# Power_Distribution_-_Motor_Interface.net
KiCad netlist of a schematic drawn in Altium Designer
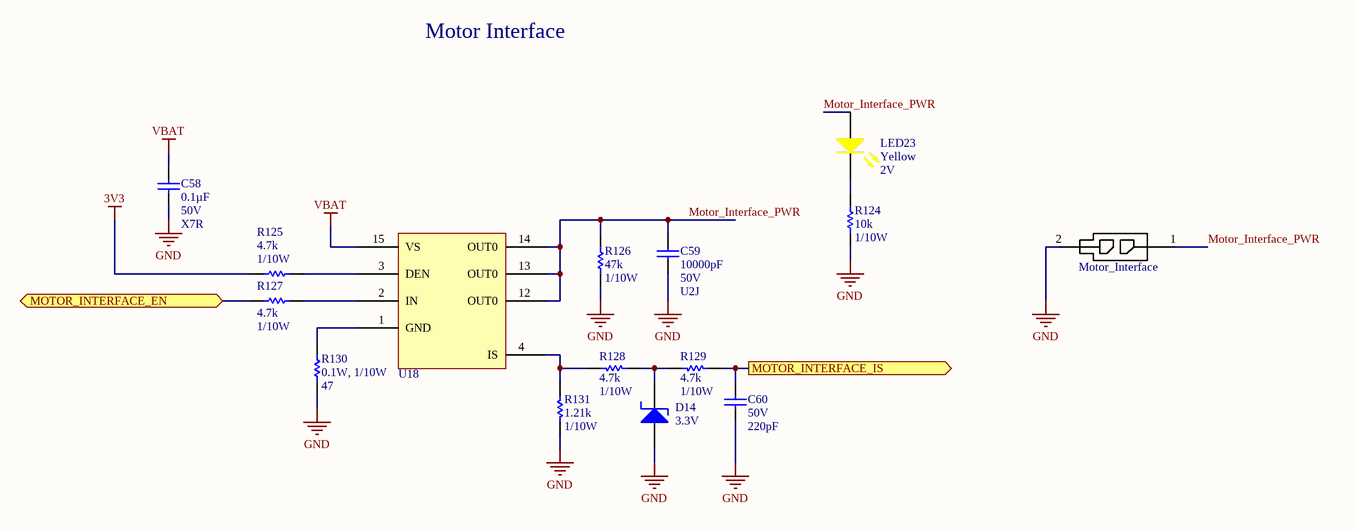
[diagram p0: Power Distribution - Motor Interface.SchDoc]

(export (version "E")
  (design (tool "Eeschema 10.0.6"))
  (components
    (comp (ref "C58")
      (value "CAP CER 0.1UF 50V 10% X7R 0603")
      (footprint "CAP, 0603")
      (description "0.10µF ±10% 50V Ceramic Capacitor X7R 0603 (1608 Metric)")
      (fields
        (field (name "TOLERANCE") "±10%")
        (field (name "CAPACITANCE") "0.1µF")
        (field (name "VOLTAGE") "50V")
        (field (name "TEMPERATURE COEFFICIENT") "X7R")
      )
      (libsource (lib "Schematic Diagrams") (part "CAP CER 0.1UF 50V 10% X7R 0603"))
    )
    (comp (ref "C59")
      (value "CAP CER 10nF 50V 5% X7R 0603")
      (footprint "CAP, 0603")
      (description "10000pF ±5% 50V Ceramic Capacitor U2J 0603 (1608 Metric)")
      (fields
        (field (name "TOLERANCE") "±5%")
        (field (name "CAPACITANCE") "10000pF")
        (field (name "VOLTAGE") "50V")
        (field (name "TEMPERATURE COEFFICIENT") "U2J")
      )
      (libsource (lib "Schematic Diagrams") (part "CAP CER 10nF 50V 5% X7R 0603"))
    )
    (comp (ref "C60")
      (value "CAP CER 220PF 50V C0G/NP0 0603")
      (footprint "CAP, 0603")
      (description "220pF ±5% 50V Ceramic Capacitor C0G, NP0 0603 (1608 Metric)")
      (fields
        (field (name "MANUFACTURER") "KEMET")
        (field (name "TOLERANCE") "5%")
        (field (name "VOLTAGE RATING") "50V")
        (field (name "CAPACITANCE") "220pF")
      )
      (libsource (lib "Schematic Diagrams") (part "CAP CER 220PF 50V C0G/NP0 0603"))
    )
    (comp (ref "D14")
      (value "DIODE ZENER 3.3V 200MW SOD323")
      (footprint "sod-323")
      (description "Zener Diode 3.3V 200mW ±5% Surface Mount SOD-323")
      (fields (field (name "VOLTAGE") "3.3V"))
      (libsource (lib "Schematic Diagrams") (part "DIODE ZENER 3.3V 200MW SOD323"))
    )
    (comp (ref "LED23")
      (value "LED YELLOW CLEAR 2.1V 0603")
      (footprint "LED_0603")
      (description "Yellow 590nm LED Indication - Discrete 2V 0603 (1608 Metric)")
      (fields
        (field (name "MANUFACTURER") "Wurth Electronics Inc.")
        (field (name "MANUFACTURER PART NUMBER") "150060YS75000")
        (field (name "COLOR") "Yellow")
        (field (name "VOLTAGE - FORWARD (VF) (TYP)") "2V")
      )
      (libsource (lib "Schematic Diagrams") (part "LED YELLOW CLEAR 2.1V 0603"))
    )
    (comp (ref "Motor_Interface")
      (value "CONN 2POS MICRO-FIT 3mm")
      (footprint "CONN, 2POS MICRO-FIT")
      (description "Connector Header Through Hole 2 position")
      (fields (field (name "MANUFACTURER") "Molex") (field (name "MANUFACTURER PART NUMBER") "43045-0227"))
      (libsource (lib "Schematic Diagrams") (part "CONN 2POS MICRO-FIT 3mm"))
    )
    (comp (ref "R124")
      (value "RES 10K OHM 1% 1/10W 0603")
      (footprint "RES, 0603")
      (description "RES SMD 10K OHM 1% 1/10W 0603")
      (fields
        (field (name "TOLERANCE") "±1%")
        (field (name "RESISTANCE") "10k")
        (field (name "POWER") "1/10W")
      )
      (libsource (lib "Schematic Diagrams") (part "RES 10K OHM 1% 1/10W 0603"))
    )
    (comp (ref "R125")
      (value "RES 4.7K OHM 1% 1/10W 0603")
      (footprint "RES, 0603")
      (description "4.7k Ohm ±1% 0.1W, 1/10W Chip Resistor 0603 (1608 Metric) Moisture Resistant Thick Film")
      (fields
        (field (name "TOLERANCE") "±1%")
        (field (name "RESISTANCE (OHMS)") "4.7k")
        (field (name "POWER (WATTS)") "1/10W")
      )
      (libsource (lib "Schematic Diagrams") (part "RES 4.7K OHM 1% 1/10W 0603"))
    )
    (comp (ref "R126")
      (value "RES 47K OHM 1% 1/10W 0603")
      (footprint "RES, 0603")
      (description "47 kOhms ±1% 0.1W, 1/10W Chip Resistor 0603 (1608 Metric) Automotive AEC-Q200 Thick Film")
      (fields
        (field (name "MANUFACTURER") "Panasonic")
        (field (name "MANUFACTURER PART NUMBER") "ERJ3EKF4702V")
        (field (name "RESISTANCE") "47k")
        (field (name "POWER RATING") "1/10W")
      )
      (libsource (lib "Schematic Diagrams") (part "RES 47K OHM 1% 1/10W 0603"))
    )
    (comp (ref "R127")
      (value "RES 4.7K OHM 1% 1/10W 0603")
      (footprint "RES, 0603")
      (description "4.7k Ohm ±1% 0.1W, 1/10W Chip Resistor 0603 (1608 Metric) Moisture Resistant Thick Film")
      (fields
        (field (name "TOLERANCE") "±1%")
        (field (name "RESISTANCE (OHMS)") "4.7k")
        (field (name "POWER (WATTS)") "1/10W")
      )
      (libsource (lib "Schematic Diagrams") (part "RES 4.7K OHM 1% 1/10W 0603"))
    )
    (comp (ref "R128")
      (value "RES 4.7K OHM 1% 1/10W 0603")
      (footprint "RES, 0603")
      (description "4.7k Ohm ±1% 0.1W, 1/10W Chip Resistor 0603 (1608 Metric) Moisture Resistant Thick Film")
      (fields
        (field (name "TOLERANCE") "±1%")
        (field (name "RESISTANCE (OHMS)") "4.7k")
        (field (name "POWER (WATTS)") "1/10W")
      )
      (libsource (lib "Schematic Diagrams") (part "RES 4.7K OHM 1% 1/10W 0603"))
    )
    (comp (ref "R129")
      (value "RES 4.7K OHM 1% 1/10W 0603")
      (footprint "RES, 0603")
      (description "4.7k Ohm ±1% 0.1W, 1/10W Chip Resistor 0603 (1608 Metric) Moisture Resistant Thick Film")
      (fields
        (field (name "TOLERANCE") "±1%")
        (field (name "RESISTANCE (OHMS)") "4.7k")
        (field (name "POWER (WATTS)") "1/10W")
      )
      (libsource (lib "Schematic Diagrams") (part "RES 4.7K OHM 1% 1/10W 0603"))
    )
    (comp (ref "R130")
      (value "RES SMD 47 OHM 1% 1/10W 0603")
      (footprint "RES, 0603")
      (fields
        (field (name "TOLERANCE") "±1%")
        (field (name "POWER (WATTS)") "0.1W, 1/10W")
        (field (name "VALUES") "47")
      )
      (libsource (lib "Schematic Diagrams") (part "RES SMD 47 OHM 1% 1/10W 0603"))
    )
    (comp (ref "R131")
      (value "RES 1.21K OHM 1% 1/10W 0603")
      (footprint "RES, 0603")
      (description "1.21k Ohm ±1% 0.1W, 1/10W Chip Resistor 0603 (1608 Metric) Moisture Resistant Thick Film")
      (fields
        (field (name "TOLERANCE") "±1%")
        (field (name "RESISTANCE") "1.21k")
        (field (name "POWER") "1/10W")
      )
      (libsource (lib "Schematic Diagrams") (part "RES 1.21K OHM 1% 1/10W 0603"))
    )
    (comp (ref "U18")
      (value "IC LOAD SWITCH BTS70401EPA PG-TSDSO-14-22")
      (footprint "IC LOAD SWITCH PG-TSDSO-14-22")
      (description "Power Switch/Driver 1:1 N-Channel 4.5A PG-TSDSO-14-22")
      (fields
        (field (name "MANUFACTURER") "Infineon")
        (field (name "MANUFACTURER PART NUMBER") "BTS70401EPAXUMA1")
      )
      (libsource (lib "Schematic Diagrams") (part "IC LOAD SWITCH BTS70401EPA PG-TSDSO-14-22"))
    )
  )
  (nets
    (net (code "1") (name "/MOTOR_INTERFACE_EN") (class "Default")
      (node (ref "R127") (pin "1") (pinfunction "1_1") (pintype "passive"))
    )
    (net (code "2") (name "/MOTOR_INTERFACE_IS") (class "Default")
      (node (ref "C60") (pin "1") (pinfunction "1_1") (pintype "passive"))
      (node (ref "R129") (pin "1") (pinfunction "1_1") (pintype "passive"))
    )
    (net (code "3") (name "/Motor_Interface_PWR") (class "Default")
      (node (ref "C59") (pin "1") (pinfunction "1_1") (pintype "passive"))
      (node (ref "LED23") (pin "1") (pinfunction "A_1") (pintype "passive"))
      (node (ref "Motor_Interface") (pin "1") (pinfunction "1_1") (pintype "passive"))
      (node (ref "R126") (pin "1") (pinfunction "1_1") (pintype "passive"))
      (node (ref "U18") (pin "12") (pinfunction "OUT0_12") (pintype "passive"))
      (node (ref "U18") (pin "13") (pinfunction "OUT0_13") (pintype "passive"))
      (node (ref "U18") (pin "14") (pinfunction "OUT0_14") (pintype "passive"))
    )
    (net (code "4") (name "3V3") (class "Default")
      (node (ref "R125") (pin "1") (pinfunction "1_1") (pintype "passive"))
    )
    (net (code "5") (name "GND") (class "Default")
      (node (ref "C58") (pin "2") (pinfunction "2_2") (pintype "passive"))
      (node (ref "C59") (pin "2") (pinfunction "2_2") (pintype "passive"))
      (node (ref "C60") (pin "2") (pinfunction "2_2") (pintype "passive"))
      (node (ref "D14") (pin "1") (pinfunction "A_1") (pintype "passive"))
      (node (ref "Motor_Interface") (pin "2") (pinfunction "2_2") (pintype "passive"))
      (node (ref "R124") (pin "2") (pinfunction "2_2") (pintype "passive"))
      (node (ref "R126") (pin "2") (pinfunction "2_2") (pintype "passive"))
      (node (ref "R130") (pin "2") (pinfunction "2_2") (pintype "passive"))
      (node (ref "R131") (pin "2") (pinfunction "2_2") (pintype "passive"))
    )
    (net (code "6") (name "Net-(D14-K)") (class "Default")
      (node (ref "D14") (pin "2") (pinfunction "K_2") (pintype "passive"))
      (node (ref "R128") (pin "1") (pinfunction "1_1") (pintype "passive"))
      (node (ref "R129") (pin "2") (pinfunction "2_2") (pintype "passive"))
    )
    (net (code "7") (name "Net-(LED23-K)") (class "Default")
      (node (ref "LED23") (pin "2") (pinfunction "K_2") (pintype "passive"))
      (node (ref "R124") (pin "1") (pinfunction "1_1") (pintype "passive"))
    )
    (net (code "8") (name "Net-(U18-DEN)") (class "Default")
      (node (ref "R125") (pin "2") (pinfunction "2_2") (pintype "passive"))
      (node (ref "U18") (pin "3") (pinfunction "DEN_3") (pintype "passive"))
    )
    (net (code "9") (name "Net-(U18-GND)") (class "Default")
      (node (ref "R130") (pin "1") (pinfunction "1_1") (pintype "passive"))
      (node (ref "U18") (pin "1") (pinfunction "GND_1") (pintype "passive"))
    )
    (net (code "10") (name "Net-(U18-IN)") (class "Default")
      (node (ref "R127") (pin "2") (pinfunction "2_2") (pintype "passive"))
      (node (ref "U18") (pin "2") (pinfunction "IN_2") (pintype "passive"))
    )
    (net (code "11") (name "Net-(U18-IS)") (class "Default")
      (node (ref "R128") (pin "2") (pinfunction "2_2") (pintype "passive"))
      (node (ref "R131") (pin "1") (pinfunction "1_1") (pintype "passive"))
      (node (ref "U18") (pin "4") (pinfunction "IS_4") (pintype "passive"))
    )
    (net (code "12") (name "VBAT") (class "Default")
      (node (ref "C58") (pin "1") (pinfunction "1_1") (pintype "passive"))
      (node (ref "U18") (pin "15") (pinfunction "VS_15") (pintype "passive"))
    )
  )
)
